# integratorSchmidtTriggerOsc.net
KiCad netlist of a schematic drawn in EAGLE
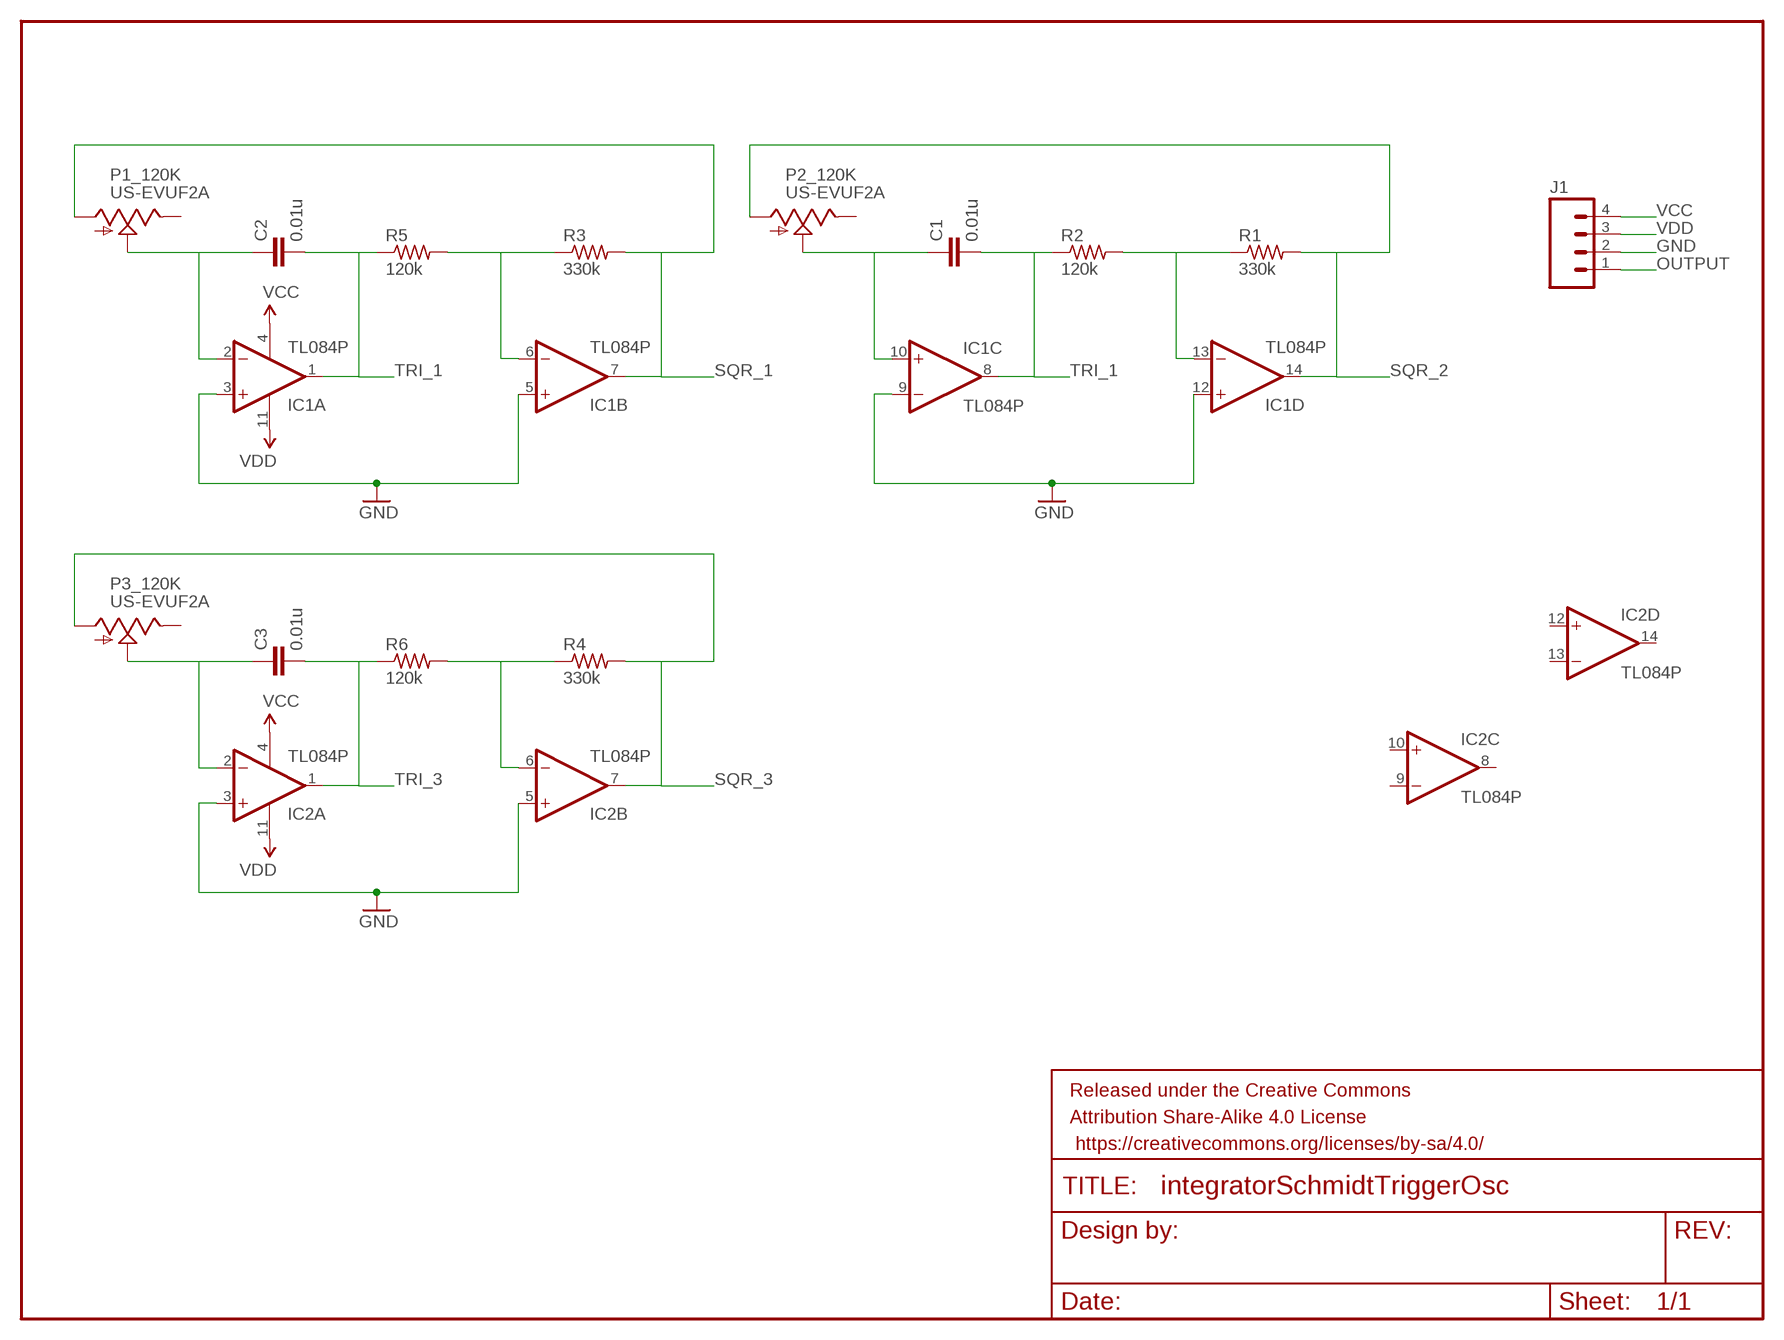
[diagram p0: schematic, sheet 1]

(export (version "E")
  (design (tool "Eeschema 10.0.6"))
  (components
    (comp (ref "C1")
      (value "0.01u")
      (footprint "eagle-import:AXIAL-5MM")
      (libsource (lib "eagle-import") (part "CAP_"))
    )
    (comp (ref "C2")
      (value "0.01u")
      (footprint "eagle-import:AXIAL-5MM")
      (libsource (lib "eagle-import") (part "CAP_"))
    )
    (comp (ref "C3")
      (value "0.01u")
      (footprint "eagle-import:AXIAL-5MM")
      (libsource (lib "eagle-import") (part "CAP_"))
    )
    (comp (ref "FRAME1")
      (value "FRAME-LETTERNO_PACKAGE")
      (footprint "eagle-import:DUMMY")
      (fields (field (name "DESIGNER") "Nobody"))
      (libsource (lib "eagle-import") (part "FRAME-LETTERNO_PACKAGE"))
    )
    (comp (ref "IC1")
      (value "TL084P")
      (footprint "eagle-import:DIL14")
      (libsource (lib "eagle-import") (part "TL084P"))
    )
    (comp (ref "IC2")
      (value "TL084P")
      (footprint "eagle-import:DIL14")
      (libsource (lib "eagle-import") (part "TL084P"))
    )
    (comp (ref "J1")
      (value "M04NO_SILK_ALL_ROUND")
      (footprint "eagle-import:1X04_NO_SILK_ALL_ROUND")
      (libsource (lib "eagle-import") (part "M04NO_SILK_ALL_ROUND"))
    )
    (comp (ref "P1_120K")
      (value "US-EVUF2A")
      (footprint "eagle-import:EVUF")
      (libsource (lib "eagle-import") (part "US-EVUAF2"))
    )
    (comp (ref "P2_120K")
      (value "US-EVUF2A")
      (footprint "eagle-import:EVUF")
      (libsource (lib "eagle-import") (part "US-EVUAF2"))
    )
    (comp (ref "P3_120K")
      (value "US-EVUF2A")
      (footprint "eagle-import:EVUF")
      (libsource (lib "eagle-import") (part "US-EVUAF2"))
    )
    (comp (ref "R1")
      (value "330k")
      (footprint "eagle-import:0204_7")
      (libsource (lib "eagle-import") (part "R-US_0204/7"))
    )
    (comp (ref "R2")
      (value "120k")
      (footprint "eagle-import:0204_7")
      (libsource (lib "eagle-import") (part "R-US_0204/7"))
    )
    (comp (ref "R3")
      (value "330k")
      (footprint "eagle-import:0204_7")
      (libsource (lib "eagle-import") (part "R-US_0204/7"))
    )
    (comp (ref "R4")
      (value "330k")
      (footprint "eagle-import:0204_7")
      (libsource (lib "eagle-import") (part "R-US_0204/7"))
    )
    (comp (ref "R5")
      (value "120k")
      (footprint "eagle-import:0204_7")
      (libsource (lib "eagle-import") (part "R-US_0204/7"))
    )
    (comp (ref "R6")
      (value "120k")
      (footprint "eagle-import:0204_7")
      (libsource (lib "eagle-import") (part "R-US_0204/7"))
    )
  )
  (nets
    (net (code "1") (name "/OUTPUT") (class "Default")
      (node (ref "J1") (pin "1") (pinfunction "1_1") (pintype "passive"))
    )
    (net (code "2") (name "/SQR_1") (class "Default")
      (node (ref "IC1") (pin "7") (pinfunction "OUT_7") (pintype "output"))
      (node (ref "P1_120K") (pin "1") (pinfunction "A_1") (pintype "passive"))
      (node (ref "R3") (pin "2") (pinfunction "2_2") (pintype "passive"))
    )
    (net (code "3") (name "/SQR_2") (class "Default")
      (node (ref "IC1") (pin "14") (pinfunction "OUT_14") (pintype "output"))
      (node (ref "P2_120K") (pin "1") (pinfunction "A_1") (pintype "passive"))
      (node (ref "R1") (pin "2") (pinfunction "2_2") (pintype "passive"))
    )
    (net (code "4") (name "/SQR_3") (class "Default")
      (node (ref "IC2") (pin "7") (pinfunction "OUT_7") (pintype "output"))
      (node (ref "P3_120K") (pin "1") (pinfunction "A_1") (pintype "passive"))
      (node (ref "R4") (pin "2") (pinfunction "2_2") (pintype "passive"))
    )
    (net (code "5") (name "/TRI_1") (class "Default")
      (node (ref "C1") (pin "P$2") (pinfunction "2_P$2") (pintype "passive"))
      (node (ref "C2") (pin "P$2") (pinfunction "2_P$2") (pintype "passive"))
      (node (ref "IC1") (pin "1") (pinfunction "OUT_1") (pintype "output"))
      (node (ref "IC1") (pin "8") (pinfunction "OUT_8") (pintype "output"))
      (node (ref "R2") (pin "1") (pinfunction "1_1") (pintype "passive"))
      (node (ref "R5") (pin "1") (pinfunction "1_1") (pintype "passive"))
    )
    (net (code "6") (name "/TRI_3") (class "Default")
      (node (ref "C3") (pin "P$2") (pinfunction "2_P$2") (pintype "passive"))
      (node (ref "IC2") (pin "1") (pinfunction "OUT_1") (pintype "output"))
      (node (ref "R6") (pin "1") (pinfunction "1_1") (pintype "passive"))
    )
    (net (code "7") (name "GND") (class "Default")
      (node (ref "IC1") (pin "12") (pinfunction "+IN_12") (pintype "input"))
      (node (ref "IC1") (pin "3") (pinfunction "+IN_3") (pintype "input"))
      (node (ref "IC1") (pin "5") (pinfunction "+IN_5") (pintype "input"))
      (node (ref "IC1") (pin "9") (pinfunction "-IN_9") (pintype "input"))
      (node (ref "IC2") (pin "3") (pinfunction "+IN_3") (pintype "input"))
      (node (ref "IC2") (pin "5") (pinfunction "+IN_5") (pintype "input"))
      (node (ref "J1") (pin "2") (pinfunction "2_2") (pintype "passive"))
    )
    (net (code "8") (name "Net-(C1-1)") (class "Default")
      (node (ref "C1") (pin "P$1") (pinfunction "1_P$1") (pintype "passive"))
      (node (ref "IC1") (pin "10") (pinfunction "+IN_10") (pintype "input"))
      (node (ref "P2_120K") (pin "2") (pinfunction "S_2") (pintype "passive"))
    )
    (net (code "9") (name "Net-(C2-1)") (class "Default")
      (node (ref "C2") (pin "P$1") (pinfunction "1_P$1") (pintype "passive"))
      (node (ref "IC1") (pin "2") (pinfunction "-IN_2") (pintype "input"))
      (node (ref "P1_120K") (pin "2") (pinfunction "S_2") (pintype "passive"))
    )
    (net (code "10") (name "Net-(C3-1)") (class "Default")
      (node (ref "C3") (pin "P$1") (pinfunction "1_P$1") (pintype "passive"))
      (node (ref "IC2") (pin "2") (pinfunction "-IN_2") (pintype "input"))
      (node (ref "P3_120K") (pin "2") (pinfunction "S_2") (pintype "passive"))
    )
    (net (code "11") (name "Net-(IC1B--IN)") (class "Default")
      (node (ref "IC1") (pin "6") (pinfunction "-IN_6") (pintype "input"))
      (node (ref "R3") (pin "1") (pinfunction "1_1") (pintype "passive"))
      (node (ref "R5") (pin "2") (pinfunction "2_2") (pintype "passive"))
    )
    (net (code "12") (name "Net-(IC1D--IN)") (class "Default")
      (node (ref "IC1") (pin "13") (pinfunction "-IN_13") (pintype "input"))
      (node (ref "R1") (pin "1") (pinfunction "1_1") (pintype "passive"))
      (node (ref "R2") (pin "2") (pinfunction "2_2") (pintype "passive"))
    )
    (net (code "13") (name "Net-(IC2B--IN)") (class "Default")
      (node (ref "IC2") (pin "6") (pinfunction "-IN_6") (pintype "input"))
      (node (ref "R4") (pin "1") (pinfunction "1_1") (pintype "passive"))
      (node (ref "R6") (pin "2") (pinfunction "2_2") (pintype "passive"))
    )
    (net (code "14") (name "VCC") (class "Default")
      (node (ref "IC1") (pin "4") (pinfunction "V+_4") (pintype "power_in"))
      (node (ref "IC2") (pin "4") (pinfunction "V+_4") (pintype "power_in"))
      (node (ref "J1") (pin "4") (pinfunction "4_4") (pintype "passive"))
    )
    (net (code "15") (name "VDD") (class "Default")
      (node (ref "IC1") (pin "11") (pinfunction "V-_11") (pintype "power_in"))
      (node (ref "IC2") (pin "11") (pinfunction "V-_11") (pintype "power_in"))
      (node (ref "J1") (pin "3") (pinfunction "3_3") (pintype "passive"))
    )
    (net (code "16") (name "unconnected-(IC2C-+IN-Pad10)") (class "Default")
      (node (ref "IC2") (pin "10") (pinfunction "+IN_10") (pintype "input"))
    )
    (net (code "17") (name "unconnected-(IC2C--IN-Pad9)") (class "Default")
      (node (ref "IC2") (pin "9") (pinfunction "-IN_9") (pintype "input"))
    )
    (net (code "18") (name "unconnected-(IC2C-OUT-Pad8)") (class "Default")
      (node (ref "IC2") (pin "8") (pinfunction "OUT_8") (pintype "output"))
    )
    (net (code "19") (name "unconnected-(IC2D-+IN-Pad12)") (class "Default")
      (node (ref "IC2") (pin "12") (pinfunction "+IN_12") (pintype "input"))
    )
    (net (code "20") (name "unconnected-(IC2D--IN-Pad13)") (class "Default")
      (node (ref "IC2") (pin "13") (pinfunction "-IN_13") (pintype "input"))
    )
    (net (code "21") (name "unconnected-(IC2D-OUT-Pad14)") (class "Default")
      (node (ref "IC2") (pin "14") (pinfunction "OUT_14") (pintype "output"))
    )
    (net (code "22") (name "unconnected-(P1_120K-E-Pad3)") (class "Default")
      (node (ref "P1_120K") (pin "3") (pinfunction "E_3") (pintype "passive"))
    )
    (net (code "23") (name "unconnected-(P2_120K-E-Pad3)") (class "Default")
      (node (ref "P2_120K") (pin "3") (pinfunction "E_3") (pintype "passive"))
    )
    (net (code "24") (name "unconnected-(P3_120K-E-Pad3)") (class "Default")
      (node (ref "P3_120K") (pin "3") (pinfunction "E_3") (pintype "passive"))
    )
  )
)
